# Single.net
KiCad netlist of a schematic drawn in Altium Designer
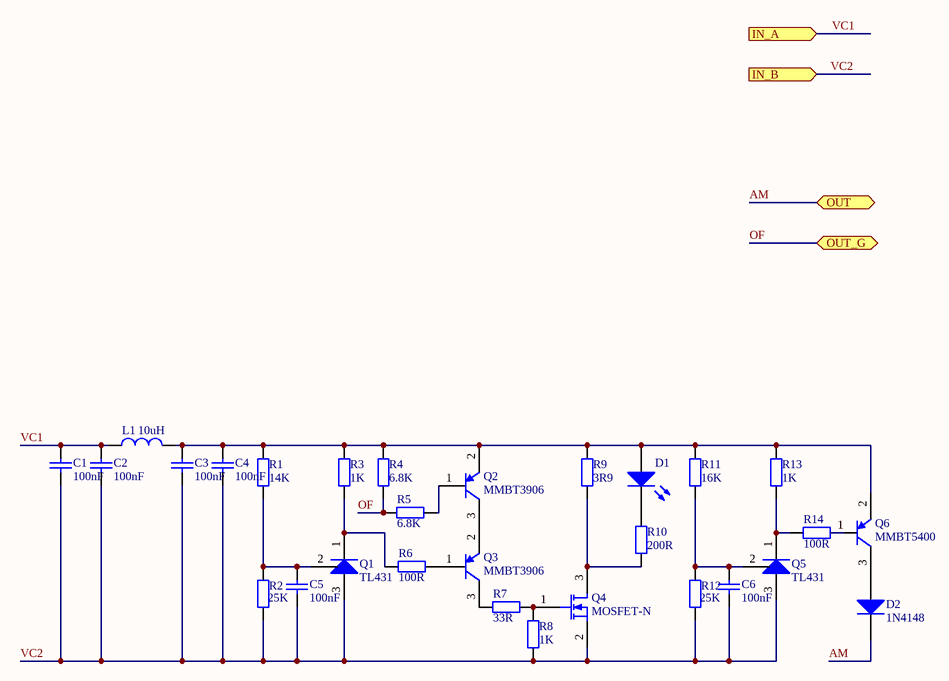
[diagram p0: Single.SchDoc]

(export (version "E")
  (design (tool "Eeschema 10.0.6"))
  (components
    (comp (ref "C1")
      (value "100nF")
      (footprint "C-0603")
      (description "贴片瓷片电容")
      (fields (field (name "Comment") "Cap-S") (field (name "PUBLISHER") "Altium Limited"))
      (libsource (lib "fszhang") (part "Cap-S"))
    )
    (comp (ref "C2")
      (value "100nF")
      (footprint "C-0603")
      (description "贴片瓷片电容")
      (fields (field (name "Comment") "Cap-S") (field (name "PUBLISHER") "Altium Limited"))
      (libsource (lib "fszhang") (part "Cap-S"))
    )
    (comp (ref "C3")
      (value "100nF")
      (footprint "C-0603")
      (description "贴片瓷片电容")
      (fields (field (name "Comment") "Cap-S") (field (name "PUBLISHER") "Altium Limited"))
      (libsource (lib "fszhang") (part "Cap-S"))
    )
    (comp (ref "C4")
      (value "100nF")
      (footprint "C-0603")
      (description "贴片瓷片电容")
      (fields (field (name "Comment") "Cap-S") (field (name "PUBLISHER") "Altium Limited"))
      (libsource (lib "fszhang") (part "Cap-S"))
    )
    (comp (ref "C5")
      (value "100nF")
      (footprint "C-0603")
      (description "贴片瓷片电容")
      (fields (field (name "Comment") "Cap-S") (field (name "PUBLISHER") "Altium Limited"))
      (libsource (lib "fszhang") (part "Cap-S"))
    )
    (comp (ref "C6")
      (value "100nF")
      (footprint "C-0603")
      (description "贴片瓷片电容")
      (fields (field (name "Comment") "Cap-S") (field (name "PUBLISHER") "Altium Limited"))
      (libsource (lib "fszhang") (part "Cap-S"))
    )
    (comp (ref "D1")
      (value "LED0")
      (footprint "LED-0805")
      (description "发光二极管")
      (fields (field (name "PUBLISHER") "Altium Limited"))
      (libsource (lib "fszhang") (part "LED0"))
    )
    (comp (ref "D2")
      (value "1N4148")
      (footprint "LED-0805")
      (description "整流二极管")
      (fields (field (name "PUBLISHER") "Altium Limited"))
      (libsource (lib "Fszhang") (part "Diode-R"))
    )
    (comp (ref "L1")
      (value "10uH")
      (footprint "0603-1")
      (description "电感")
      (fields (field (name "Comment") "Inductor") (field (name "PUBLISHER") "Altium Limited"))
      (libsource (lib "fszhang") (part "Inductor"))
    )
    (comp (ref "Q1")
      (value "TL431")
      (footprint "SOT23-3")
      (description "可控精密稳压源")
      (libsource (lib "fszhang") (part "TL431"))
    )
    (comp (ref "Q2")
      (value "MMBT3906")
      (footprint "SOT23-3")
      (description "贴片三极管")
      (fields (field (name "PUBLISHER") "Altium Limited"))
      (libsource (lib "Fszhang") (part "PNP1"))
    )
    (comp (ref "Q3")
      (value "MMBT3906")
      (footprint "SOT23-3")
      (description "贴片三极管")
      (fields (field (name "PUBLISHER") "Altium Limited"))
      (libsource (lib "Fszhang") (part "PNP1"))
    )
    (comp (ref "Q4")
      (value "MOSFET-N")
      (footprint "SOT23-3")
      (description "MOSFET")
      (fields (field (name "PUBLISHER") "Altium Limited"))
      (libsource (lib "Fszhang") (part "MOSFET-N1"))
    )
    (comp (ref "Q5")
      (value "TL431")
      (footprint "SOT23-3")
      (description "可控精密稳压源")
      (libsource (lib "fszhang") (part "TL431"))
    )
    (comp (ref "Q6")
      (value "MMBT5400")
      (footprint "SOT23-3")
      (description "贴片三极管")
      (fields (field (name "PUBLISHER") "Altium Limited"))
      (libsource (lib "Fszhang") (part "PNP1"))
    )
    (comp (ref "R1")
      (value "14K")
      (footprint "0603-1")
      (description "贴片电阻")
      (fields (field (name "Comment") "Res1") (field (name "PUBLISHER") "Altium Limited"))
      (libsource (lib "") (part "Res1_1"))
    )
    (comp (ref "R2")
      (value "25K")
      (footprint "0603-1")
      (description "贴片电阻")
      (fields (field (name "Comment") "Res1") (field (name "PUBLISHER") "Altium Limited"))
      (libsource (lib "") (part "Res1_1"))
    )
    (comp (ref "R3")
      (value "1K")
      (footprint "0603-1")
      (description "贴片电阻")
      (fields (field (name "Comment") "Res1") (field (name "PUBLISHER") "Altium Limited"))
      (libsource (lib "") (part "Res1_1"))
    )
    (comp (ref "R4")
      (value "6.8K")
      (footprint "0603-1")
      (description "贴片电阻")
      (fields (field (name "Comment") "Res1") (field (name "PUBLISHER") "Altium Limited"))
      (libsource (lib "") (part "Res1_3"))
    )
    (comp (ref "R5")
      (value "6.8K")
      (footprint "0603-1")
      (description "贴片电阻")
      (fields (field (name "Comment") "Res1") (field (name "PUBLISHER") "Altium Limited"))
      (libsource (lib "") (part "Res1_2"))
    )
    (comp (ref "R6")
      (value "100R")
      (footprint "0603-1")
      (description "贴片电阻")
      (fields (field (name "Comment") "Res1") (field (name "PUBLISHER") "Altium Limited"))
      (libsource (lib "") (part "Res1_2"))
    )
    (comp (ref "R7")
      (value "33R")
      (footprint "0603-1")
      (description "贴片电阻")
      (fields (field (name "Comment") "Res1") (field (name "PUBLISHER") "Altium Limited"))
      (libsource (lib "Fszhang") (part "Res1"))
    )
    (comp (ref "R8")
      (value "1K")
      (footprint "0603-1")
      (description "贴片电阻")
      (fields (field (name "Comment") "Res1") (field (name "PUBLISHER") "Altium Limited"))
      (libsource (lib "") (part "Res1_1"))
    )
    (comp (ref "R9")
      (value "3R9")
      (footprint "AXIAL-1.0")
      (description "贴片电阻")
      (fields (field (name "Comment") "Res1") (field (name "PUBLISHER") "Altium Limited"))
      (libsource (lib "") (part "Res1_1"))
    )
    (comp (ref "R10")
      (value "200R")
      (footprint "0603-1")
      (description "贴片电阻")
      (fields (field (name "Comment") "Res1") (field (name "PUBLISHER") "Altium Limited"))
      (libsource (lib "") (part "Res1_1"))
    )
    (comp (ref "R11")
      (value "16K")
      (footprint "0603-1")
      (description "贴片电阻")
      (fields (field (name "Comment") "Res1") (field (name "PUBLISHER") "Altium Limited"))
      (libsource (lib "") (part "Res1_1"))
    )
    (comp (ref "R12")
      (value "25K")
      (footprint "0603-1")
      (description "贴片电阻")
      (fields (field (name "Comment") "Res1") (field (name "PUBLISHER") "Altium Limited"))
      (libsource (lib "") (part "Res1_1"))
    )
    (comp (ref "R13")
      (value "1K")
      (footprint "0603-1")
      (description "贴片电阻")
      (fields (field (name "Comment") "Res1") (field (name "PUBLISHER") "Altium Limited"))
      (libsource (lib "") (part "Res1_1"))
    )
    (comp (ref "R14")
      (value "100R")
      (footprint "0603-1")
      (description "贴片电阻")
      (fields (field (name "Comment") "Res1") (field (name "PUBLISHER") "Altium Limited"))
      (libsource (lib "") (part "Res1_2"))
    )
  )
  (nets
    (net (code "1") (name "/AM") (class "Default")
      (node (ref "D2") (pin "2") (pinfunction "K_2") (pintype "passive"))
    )
    (net (code "2") (name "/OF") (class "Default")
      (node (ref "R4") (pin "2") (pinfunction "2_2") (pintype "passive"))
      (node (ref "R5") (pin "2") (pinfunction "2_2") (pintype "passive"))
    )
    (net (code "3") (name "/VC1") (class "Default")
      (node (ref "C1") (pin "2") (pinfunction "2_2") (pintype "passive"))
      (node (ref "C2") (pin "2") (pinfunction "2_2") (pintype "passive"))
      (node (ref "L1") (pin "1") (pinfunction "1_1") (pintype "passive"))
    )
    (net (code "4") (name "/VC2") (class "Default")
      (node (ref "C1") (pin "1") (pinfunction "1_1") (pintype "passive"))
      (node (ref "C2") (pin "1") (pinfunction "1_1") (pintype "passive"))
      (node (ref "C3") (pin "1") (pinfunction "1_1") (pintype "passive"))
      (node (ref "C4") (pin "1") (pinfunction "1_1") (pintype "passive"))
      (node (ref "C5") (pin "1") (pinfunction "1_1") (pintype "passive"))
      (node (ref "C6") (pin "1") (pinfunction "1_1") (pintype "passive"))
      (node (ref "Q1") (pin "3") (pinfunction "A_3") (pintype "passive"))
      (node (ref "Q4") (pin "2") (pinfunction "S_2") (pintype "passive"))
      (node (ref "Q5") (pin "3") (pinfunction "A_3") (pintype "passive"))
      (node (ref "R12") (pin "1") (pinfunction "1_1") (pintype "passive"))
      (node (ref "R2") (pin "1") (pinfunction "1_1") (pintype "passive"))
      (node (ref "R8") (pin "1") (pinfunction "1_1") (pintype "passive"))
    )
    (net (code "5") (name "Net-(D1-A)") (class "Default")
      (node (ref "C3") (pin "2") (pinfunction "2_2") (pintype "passive"))
      (node (ref "C4") (pin "2") (pinfunction "2_2") (pintype "passive"))
      (node (ref "D1") (pin "1") (pinfunction "A_1") (pintype "passive"))
      (node (ref "L1") (pin "2") (pinfunction "2_2") (pintype "passive"))
      (node (ref "Q2") (pin "2") (pinfunction "E_2") (pintype "passive"))
      (node (ref "Q6") (pin "2") (pinfunction "E_2") (pintype "passive"))
      (node (ref "R1") (pin "2") (pinfunction "2_2") (pintype "passive"))
      (node (ref "R11") (pin "2") (pinfunction "2_2") (pintype "passive"))
      (node (ref "R13") (pin "2") (pinfunction "2_2") (pintype "passive"))
      (node (ref "R3") (pin "2") (pinfunction "2_2") (pintype "passive"))
      (node (ref "R4") (pin "1") (pinfunction "1_1") (pintype "passive"))
      (node (ref "R9") (pin "2") (pinfunction "2_2") (pintype "passive"))
    )
    (net (code "6") (name "Net-(D1-K)") (class "Default")
      (node (ref "D1") (pin "2") (pinfunction "K_2") (pintype "passive"))
      (node (ref "R10") (pin "2") (pinfunction "2_2") (pintype "passive"))
    )
    (net (code "7") (name "Net-(D2-A)") (class "Default")
      (node (ref "D2") (pin "1") (pinfunction "A_1") (pintype "passive"))
      (node (ref "Q6") (pin "3") (pinfunction "C_3") (pintype "passive"))
    )
    (net (code "8") (name "Net-(Q1-K)") (class "Default")
      (node (ref "Q1") (pin "1") (pinfunction "K_1") (pintype "passive"))
      (node (ref "R3") (pin "1") (pinfunction "1_1") (pintype "passive"))
      (node (ref "R6") (pin "2") (pinfunction "2_2") (pintype "passive"))
    )
    (net (code "9") (name "Net-(Q1-R)") (class "Default")
      (node (ref "C5") (pin "2") (pinfunction "2_2") (pintype "passive"))
      (node (ref "Q1") (pin "2") (pinfunction "R_2") (pintype "passive"))
      (node (ref "R1") (pin "1") (pinfunction "1_1") (pintype "passive"))
      (node (ref "R2") (pin "2") (pinfunction "2_2") (pintype "passive"))
    )
    (net (code "10") (name "Net-(Q2-B)") (class "Default")
      (node (ref "Q2") (pin "1") (pinfunction "B_1") (pintype "passive"))
      (node (ref "R5") (pin "1") (pinfunction "1_1") (pintype "passive"))
    )
    (net (code "11") (name "Net-(Q2-C)") (class "Default")
      (node (ref "Q2") (pin "3") (pinfunction "C_3") (pintype "passive"))
      (node (ref "Q3") (pin "2") (pinfunction "E_2") (pintype "passive"))
    )
    (net (code "12") (name "Net-(Q3-B)") (class "Default")
      (node (ref "Q3") (pin "1") (pinfunction "B_1") (pintype "passive"))
      (node (ref "R6") (pin "1") (pinfunction "1_1") (pintype "passive"))
    )
    (net (code "13") (name "Net-(Q3-C)") (class "Default")
      (node (ref "Q3") (pin "3") (pinfunction "C_3") (pintype "passive"))
      (node (ref "R7") (pin "1") (pinfunction "1_1") (pintype "passive"))
    )
    (net (code "14") (name "Net-(Q4-D)") (class "Default")
      (node (ref "Q4") (pin "3") (pinfunction "D_3") (pintype "passive"))
      (node (ref "R10") (pin "1") (pinfunction "1_1") (pintype "passive"))
      (node (ref "R9") (pin "1") (pinfunction "1_1") (pintype "passive"))
    )
    (net (code "15") (name "Net-(Q4-G)") (class "Default")
      (node (ref "Q4") (pin "1") (pinfunction "G_1") (pintype "passive"))
      (node (ref "R7") (pin "2") (pinfunction "2_2") (pintype "passive"))
      (node (ref "R8") (pin "2") (pinfunction "2_2") (pintype "passive"))
    )
    (net (code "16") (name "Net-(Q5-K)") (class "Default")
      (node (ref "Q5") (pin "1") (pinfunction "K_1") (pintype "passive"))
      (node (ref "R13") (pin "1") (pinfunction "1_1") (pintype "passive"))
      (node (ref "R14") (pin "2") (pinfunction "2_2") (pintype "passive"))
    )
    (net (code "17") (name "Net-(Q5-R)") (class "Default")
      (node (ref "C6") (pin "2") (pinfunction "2_2") (pintype "passive"))
      (node (ref "Q5") (pin "2") (pinfunction "R_2") (pintype "passive"))
      (node (ref "R11") (pin "1") (pinfunction "1_1") (pintype "passive"))
      (node (ref "R12") (pin "2") (pinfunction "2_2") (pintype "passive"))
    )
    (net (code "18") (name "Net-(Q6-B)") (class "Default")
      (node (ref "Q6") (pin "1") (pinfunction "B_1") (pintype "passive"))
      (node (ref "R14") (pin "1") (pinfunction "1_1") (pintype "passive"))
    )
  )
)
